# AminMourad_weatherstation__PCB_Altium__S.net
KiCad netlist of a schematic drawn in Altium Designer
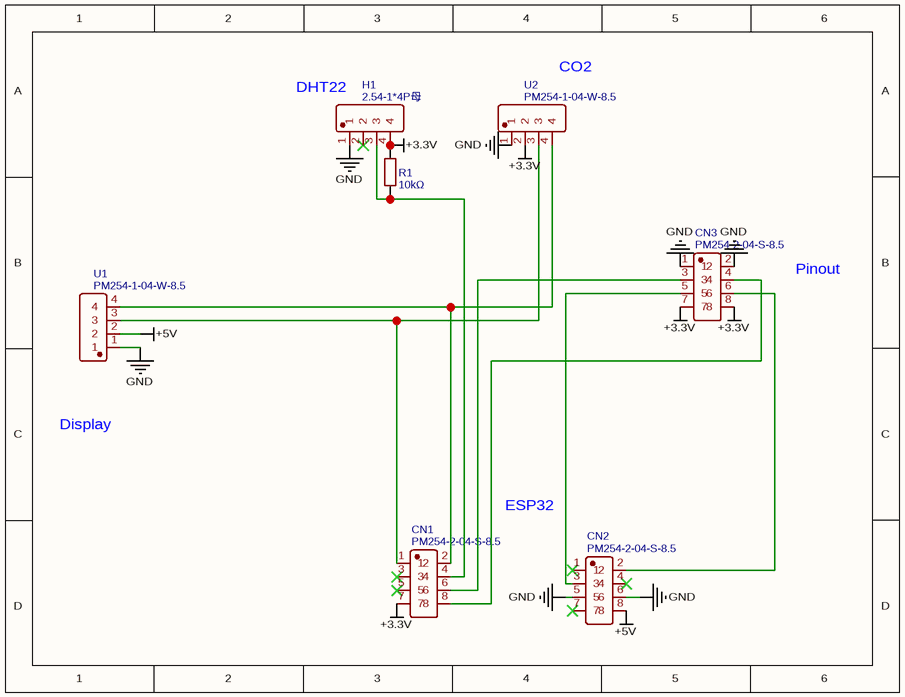
[diagram p0: AminMourad_weatherstation__PCB_Altium__Sheet_1_2024-12-12.schdoc]

(export (version "E")
  (design (tool "Eeschema 10.0.6"))
  (components
    (comp (ref "CN1")
      (value "PM254-2-04-S-8.5")
      (fields (field (name "MANUFACTURER") "HCTL(华灿天禄)") (field (name "CONTRIBUTOR") "lcsc"))
      (libsource (lib "altium-import") (part "root_0_PM254-2-04-S-8.5_"))
    )
    (comp (ref "CN2")
      (value "PM254-2-04-S-8.5")
      (fields (field (name "MANUFACTURER") "HCTL(华灿天禄)") (field (name "CONTRIBUTOR") "lcsc"))
      (libsource (lib "altium-import") (part "root_0_PM254-2-04-S-8.5_"))
    )
    (comp (ref "CN3")
      (value "PM254-2-04-S-8.5")
      (fields (field (name "MANUFACTURER") "HCTL(华灿天禄)") (field (name "CONTRIBUTOR") "lcsc"))
      (libsource (lib "altium-import") (part "root_0_PM254-2-04-S-8.5_"))
    )
    (comp (ref "H1")
      (value "2.54-1*4P母")
      (fields (field (name "MANUFACTURER") "BOOMELE(博穆精密)") (field (name "CONTRIBUTOR") "LCSC"))
      (libsource (lib "altium-import") (part "root_1_2.54-1*4P母_"))
    )
    (comp (ref "R1")
      (value "10kΩ")
      (fields
        (field (name "MANUFACTURER") "UNI-ROYAL(厚声)")
        (field (name "MANUFACTURER PART") "0603WAF1002T5E")
      )
      (libsource (lib "altium-import") (part "root_1_10kΩ_"))
    )
    (comp (ref "U1")
      (value "PM254-1-04-W-8.5")
      (fields (field (name "MANUFACTURER") "HCTL(华灿天禄)") (field (name "CONTRIBUTOR") "LCSC"))
      (libsource (lib "altium-import") (part "root_2_PM254-1-04-W-8.5_"))
    )
    (comp (ref "U2")
      (value "PM254-1-04-W-8.5")
      (fields (field (name "MANUFACTURER") "HCTL(华灿天禄)") (field (name "CONTRIBUTOR") "LCSC"))
      (libsource (lib "altium-import") (part "root_1_PM254-1-04-W-8.5_"))
    )
  )
  (nets
    (net (code "1") (name "+3.3V") (class "Default")
      (node (ref "CN1") (pin "7") (pinfunction "7_7") (pintype "passive"))
      (node (ref "CN3") (pin "7") (pinfunction "7_7") (pintype "passive"))
      (node (ref "CN3") (pin "8") (pinfunction "8_8") (pintype "passive"))
      (node (ref "H1") (pin "4") (pinfunction "4_4") (pintype "passive"))
      (node (ref "R1") (pin "2") (pinfunction "2_2") (pintype "passive"))
      (node (ref "U2") (pin "2") (pinfunction "2_2") (pintype "passive"))
    )
    (net (code "2") (name "+5V") (class "Default")
      (node (ref "CN2") (pin "8") (pinfunction "8_8") (pintype "passive"))
      (node (ref "U1") (pin "2") (pinfunction "2_2") (pintype "passive"))
    )
    (net (code "3") (name "GND") (class "Default")
      (node (ref "CN2") (pin "5") (pinfunction "5_5") (pintype "passive"))
      (node (ref "CN2") (pin "6") (pinfunction "6_6") (pintype "passive"))
      (node (ref "CN3") (pin "1") (pinfunction "1_1") (pintype "passive"))
      (node (ref "CN3") (pin "2") (pinfunction "2_2") (pintype "passive"))
      (node (ref "H1") (pin "1") (pinfunction "1_1") (pintype "passive"))
      (node (ref "U1") (pin "1") (pinfunction "1_1") (pintype "passive"))
      (node (ref "U2") (pin "1") (pinfunction "1_1") (pintype "passive"))
    )
    (net (code "4") (name "Net-(CN1-Pad1)") (class "Default")
      (node (ref "CN1") (pin "1") (pinfunction "1_1") (pintype "passive"))
      (node (ref "U1") (pin "3") (pinfunction "3_3") (pintype "passive"))
      (node (ref "U2") (pin "3") (pinfunction "3_3") (pintype "passive"))
    )
    (net (code "5") (name "Net-(CN1-Pad2)") (class "Default")
      (node (ref "CN1") (pin "2") (pinfunction "2_2") (pintype "passive"))
      (node (ref "U1") (pin "4") (pinfunction "4_4") (pintype "passive"))
      (node (ref "U2") (pin "4") (pinfunction "4_4") (pintype "passive"))
    )
    (net (code "6") (name "Net-(CN1-Pad4)") (class "Default")
      (node (ref "CN1") (pin "4") (pinfunction "4_4") (pintype "passive"))
      (node (ref "H1") (pin "3") (pinfunction "3_3") (pintype "passive"))
      (node (ref "R1") (pin "1") (pinfunction "1_1") (pintype "passive"))
    )
    (net (code "7") (name "Net-(CN1-Pad6)") (class "Default")
      (node (ref "CN1") (pin "6") (pinfunction "6_6") (pintype "passive"))
      (node (ref "CN3") (pin "3") (pinfunction "3_3") (pintype "passive"))
    )
    (net (code "8") (name "Net-(CN1-Pad8)") (class "Default")
      (node (ref "CN1") (pin "8") (pinfunction "8_8") (pintype "passive"))
      (node (ref "CN3") (pin "4") (pinfunction "4_4") (pintype "passive"))
    )
    (net (code "9") (name "Net-(CN2-Pad2)") (class "Default")
      (node (ref "CN2") (pin "2") (pinfunction "2_2") (pintype "passive"))
      (node (ref "CN3") (pin "6") (pinfunction "6_6") (pintype "passive"))
    )
    (net (code "10") (name "Net-(CN2-Pad3)") (class "Default")
      (node (ref "CN2") (pin "3") (pinfunction "3_3") (pintype "passive"))
      (node (ref "CN3") (pin "5") (pinfunction "5_5") (pintype "passive"))
    )
    (net (code "11") (name "unconnected-(CN1-Pad3)") (class "Default")
      (node (ref "CN1") (pin "3") (pinfunction "3_3") (pintype "passive+no_connect"))
    )
    (net (code "12") (name "unconnected-(CN1-Pad5)") (class "Default")
      (node (ref "CN1") (pin "5") (pinfunction "5_5") (pintype "passive+no_connect"))
    )
    (net (code "13") (name "unconnected-(CN2-Pad1)") (class "Default")
      (node (ref "CN2") (pin "1") (pinfunction "1_1") (pintype "passive+no_connect"))
    )
    (net (code "14") (name "unconnected-(CN2-Pad4)") (class "Default")
      (node (ref "CN2") (pin "4") (pinfunction "4_4") (pintype "passive+no_connect"))
    )
    (net (code "15") (name "unconnected-(CN2-Pad7)") (class "Default")
      (node (ref "CN2") (pin "7") (pinfunction "7_7") (pintype "passive+no_connect"))
    )
    (net (code "16") (name "unconnected-(H1-Pad2)") (class "Default")
      (node (ref "H1") (pin "2") (pinfunction "2_2") (pintype "passive+no_connect"))
    )
  )
)
